# W070.net
KiCad netlist of a schematic drawn in EAGLE
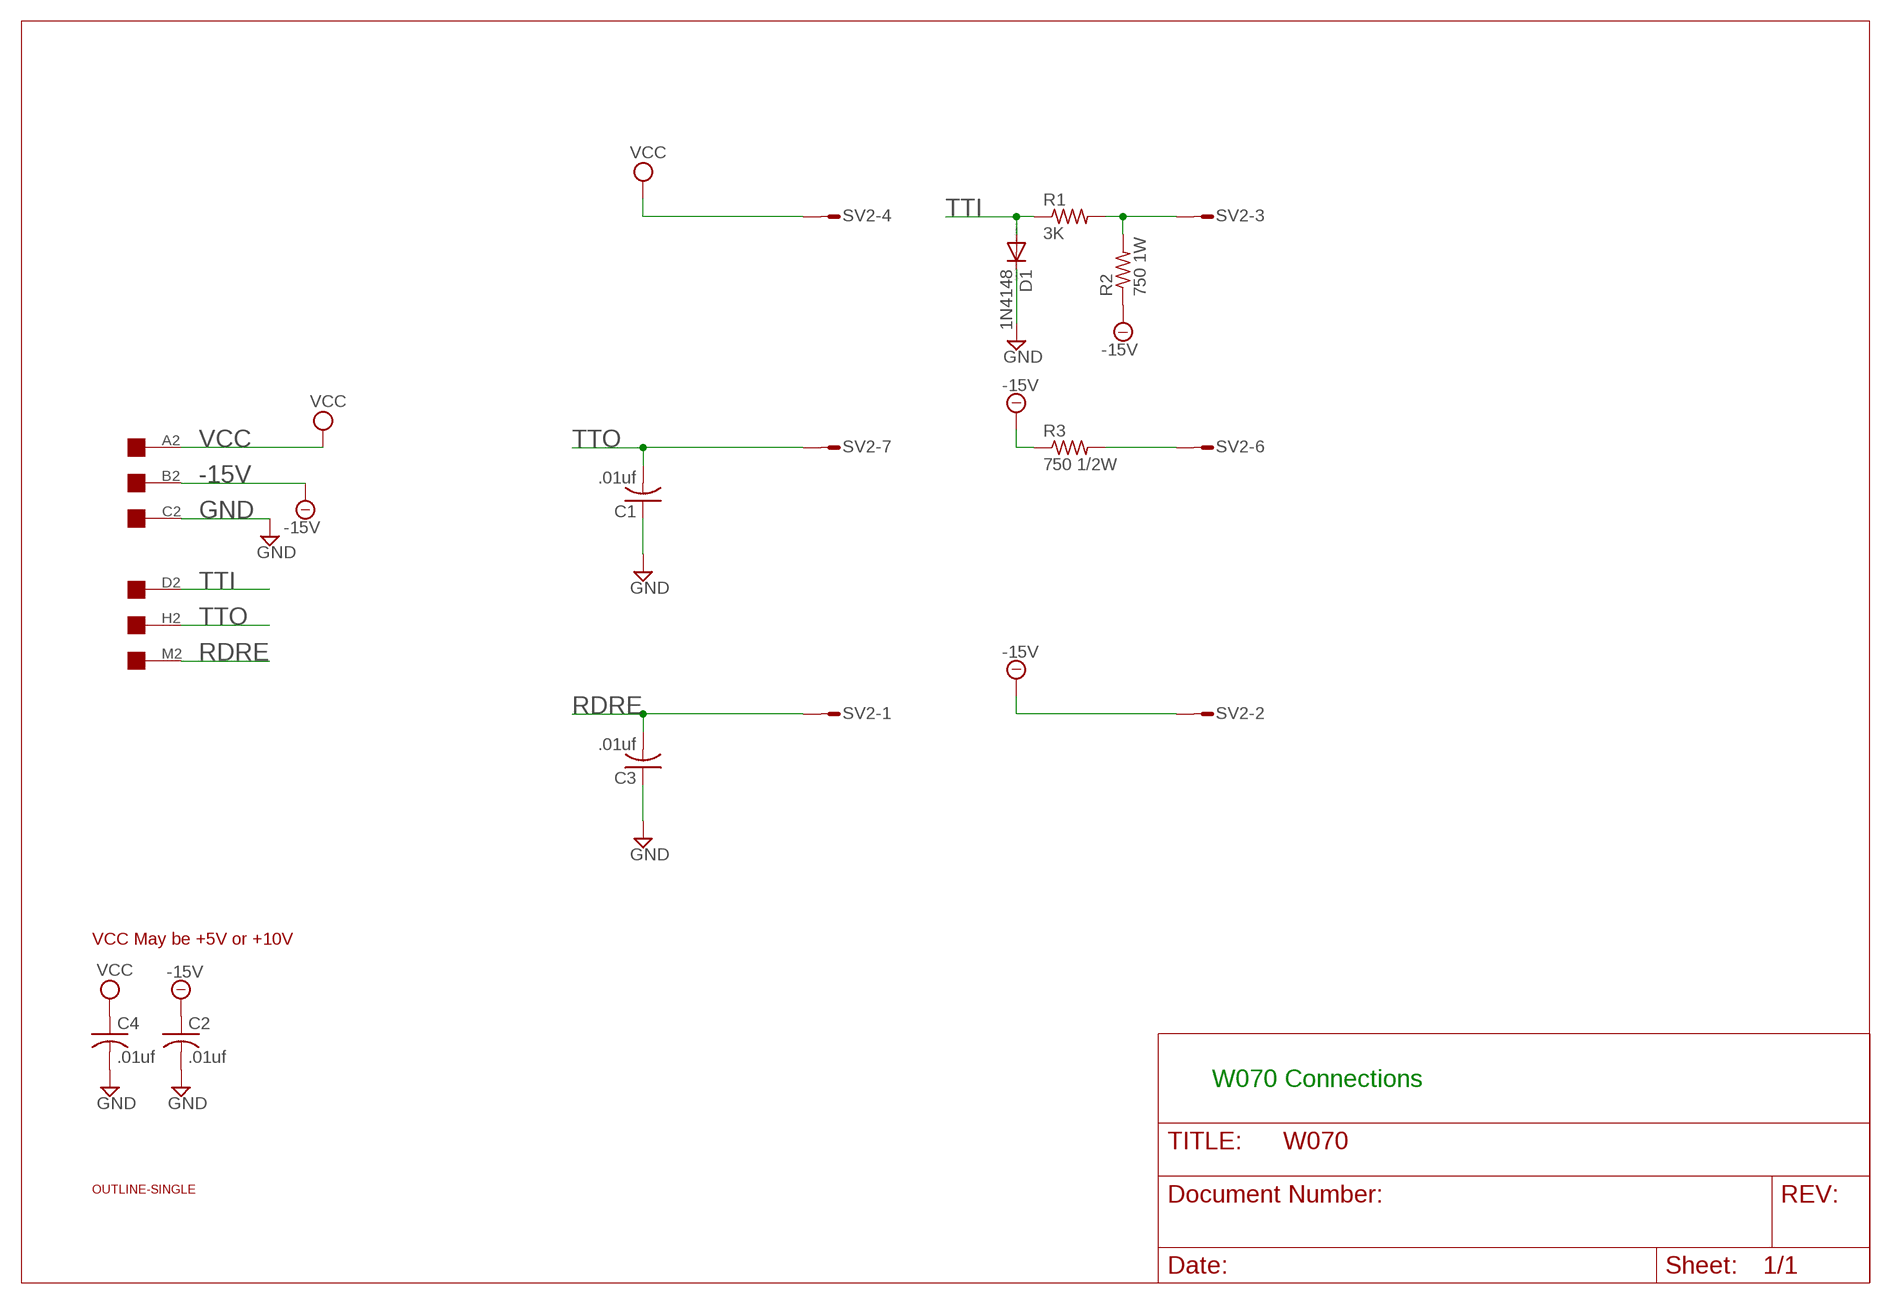
[diagram p0: schematic, sheet 1]

(export (version "E")
  (design (tool "Eeschema 10.0.6"))
  (components
    (comp (ref "C1")
      (value ".01uf")
      (footprint "eagle-import:C050-025X075")
      (libsource (lib "eagle-import") (part "C-US050-025X075"))
    )
    (comp (ref "C2")
      (value ".01uf")
      (footprint "eagle-import:C050-025X075")
      (libsource (lib "eagle-import") (part "C-US050-025X075"))
    )
    (comp (ref "C3")
      (value ".01uf")
      (footprint "eagle-import:C050-025X075")
      (libsource (lib "eagle-import") (part "C-US050-025X075"))
    )
    (comp (ref "C4")
      (value ".01uf")
      (footprint "eagle-import:C050-025X075")
      (libsource (lib "eagle-import") (part "C-US050-025X075"))
    )
    (comp (ref "D1")
      (value "1N4148")
      (footprint "eagle-import:DO35-10")
      (libsource (lib "eagle-import") (part "1N4148DO35-10"))
    )
    (comp (ref "EDGE")
      (value "EDGE-1")
      (footprint "eagle-import:EDGE-CON1")
      (libsource (lib "eagle-import") (part "EDGE-1"))
    )
    (comp (ref "R1")
      (value "3K")
      (footprint "eagle-import:0207_10")
      (libsource (lib "eagle-import") (part "R-US_0207/10"))
    )
    (comp (ref "R2")
      (value "750 1W")
      (footprint "eagle-import:0309_12")
      (libsource (lib "eagle-import") (part "R-US_0309/12"))
    )
    (comp (ref "R3")
      (value "750 1/2W")
      (footprint "eagle-import:0309_12")
      (libsource (lib "eagle-import") (part "R-US_0309/12"))
    )
    (comp (ref "SV2")
      (value "L08P")
      (footprint "eagle-import:L08P")
      (libsource (lib "eagle-import") (part "L08P"))
    )
    (comp (ref "U$1")
      (value "OUTLINE-SINGLE")
      (footprint "eagle-import:SINGLE")
      (libsource (lib "eagle-import") (part "OUTLINE-SINGLE"))
    )
  )
  (nets
    (net (code "1") (name "-15V") (class "Default")
      (node (ref "C2") (pin "1") (pinfunction "1_1") (pintype "passive"))
      (node (ref "EDGE") (pin "B2") (pinfunction "1_B2") (pintype "bidirectional"))
      (node (ref "R2") (pin "1") (pinfunction "1_1") (pintype "passive"))
      (node (ref "R3") (pin "1") (pinfunction "1_1") (pintype "passive"))
      (node (ref "SV2") (pin "2") (pinfunction "S_2") (pintype "passive"))
    )
    (net (code "2") (name "/RDRE") (class "Default")
      (node (ref "C3") (pin "2") (pinfunction "2_2") (pintype "passive"))
      (node (ref "EDGE") (pin "M2") (pinfunction "1_M2") (pintype "bidirectional"))
      (node (ref "SV2") (pin "1") (pinfunction "S_1") (pintype "passive"))
    )
    (net (code "3") (name "/TTI") (class "Default")
      (node (ref "D1") (pin "A") (pinfunction "A_A") (pintype "passive"))
      (node (ref "EDGE") (pin "D2") (pinfunction "1_D2") (pintype "bidirectional"))
      (node (ref "R1") (pin "1") (pinfunction "1_1") (pintype "passive"))
    )
    (net (code "4") (name "/TTO") (class "Default")
      (node (ref "C1") (pin "2") (pinfunction "2_2") (pintype "passive"))
      (node (ref "EDGE") (pin "H2") (pinfunction "1_H2") (pintype "bidirectional"))
      (node (ref "SV2") (pin "7") (pinfunction "S_7") (pintype "passive"))
    )
    (net (code "5") (name "GND") (class "Default")
      (node (ref "C1") (pin "1") (pinfunction "1_1") (pintype "passive"))
      (node (ref "C2") (pin "2") (pinfunction "2_2") (pintype "passive"))
      (node (ref "C3") (pin "1") (pinfunction "1_1") (pintype "passive"))
      (node (ref "C4") (pin "2") (pinfunction "2_2") (pintype "passive"))
      (node (ref "D1") (pin "C") (pinfunction "C_C") (pintype "passive"))
      (node (ref "EDGE") (pin "C2") (pinfunction "1_C2") (pintype "bidirectional"))
    )
    (net (code "6") (name "Net-(SV2C-S)") (class "Default")
      (node (ref "R1") (pin "2") (pinfunction "2_2") (pintype "passive"))
      (node (ref "R2") (pin "2") (pinfunction "2_2") (pintype "passive"))
      (node (ref "SV2") (pin "3") (pinfunction "S_3") (pintype "passive"))
    )
    (net (code "7") (name "Net-(SV2F-S)") (class "Default")
      (node (ref "R3") (pin "2") (pinfunction "2_2") (pintype "passive"))
      (node (ref "SV2") (pin "6") (pinfunction "S_6") (pintype "passive"))
    )
    (net (code "8") (name "VCC") (class "Default")
      (node (ref "C4") (pin "1") (pinfunction "1_1") (pintype "passive"))
      (node (ref "EDGE") (pin "A2") (pinfunction "1_A2") (pintype "bidirectional"))
      (node (ref "SV2") (pin "4") (pinfunction "S_4") (pintype "passive"))
    )
  )
)
